# Ethernet.net
KiCad netlist of a schematic drawn in Altium Designer
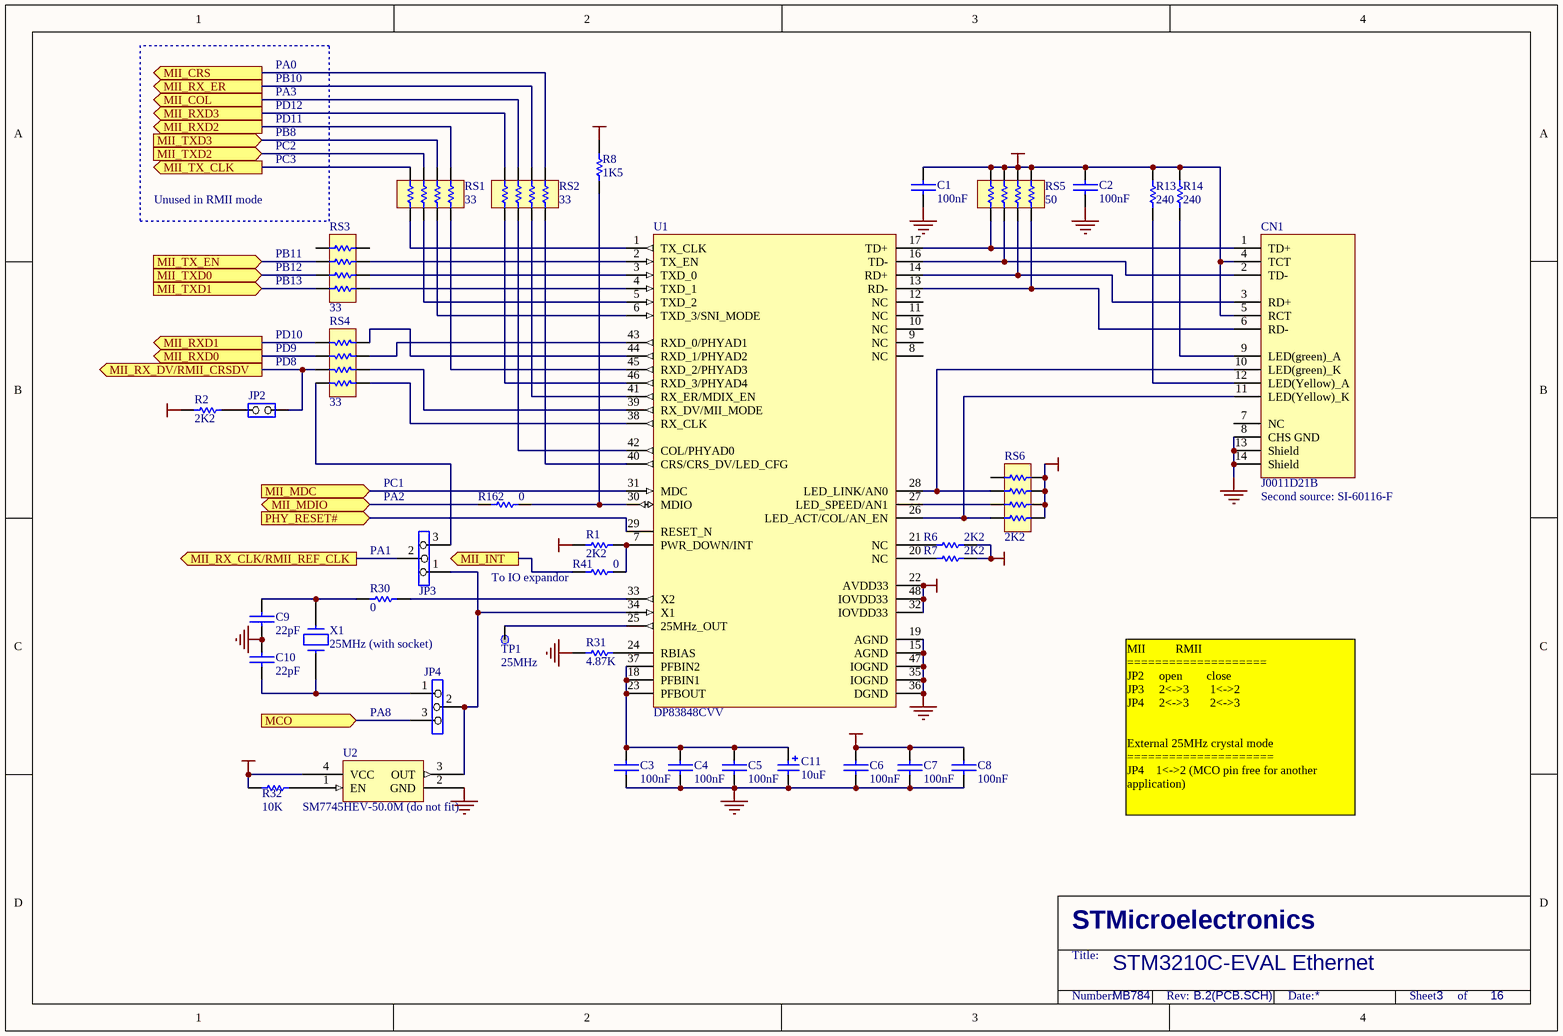
[diagram p0: Ethernet.SchDoc]

(export (version "E")
  (design (tool "Eeschema 10.0.6"))
  (components
    (comp (ref "C1")
      (value "100nF")
      (footprint "0603C")
      (description "Capacitor")
      (libsource (lib "*") (part "CAP"))
    )
    (comp (ref "C2")
      (value "100nF")
      (footprint "0603C")
      (description "Capacitor")
      (libsource (lib "*") (part "CAP"))
    )
    (comp (ref "C3")
      (value "100nF")
      (footprint "0603C")
      (description "Capacitor")
      (libsource (lib "*") (part "CAP"))
    )
    (comp (ref "C4")
      (value "100nF")
      (footprint "0603C")
      (description "Capacitor")
      (libsource (lib "*") (part "CAP"))
    )
    (comp (ref "C5")
      (value "100nF")
      (footprint "0603C")
      (description "Capacitor")
      (libsource (lib "*") (part "CAP"))
    )
    (comp (ref "C6")
      (value "100nF")
      (footprint "0603C")
      (description "Capacitor")
      (libsource (lib "*") (part "CAP"))
    )
    (comp (ref "C7")
      (value "100nF")
      (footprint "0603C")
      (description "Capacitor")
      (libsource (lib "*") (part "CAP"))
    )
    (comp (ref "C8")
      (value "100nF")
      (footprint "0603C")
      (description "Capacitor")
      (libsource (lib "*") (part "CAP"))
    )
    (comp (ref "C9")
      (value "22pF")
      (footprint "0603R")
      (description "Capacitor")
      (libsource (lib "*") (part "CAP"))
    )
    (comp (ref "C10")
      (value "22pF")
      (footprint "0603R")
      (description "Capacitor")
      (libsource (lib "*") (part "CAP"))
    )
    (comp (ref "C11")
      (value "10uF")
      (footprint "TAN-A")
      (description "Polarized Capacitor (Radial)")
      (fields (field (name "PUBLISHER") "Altium Limited"))
      (libsource (lib "Miscellaneous Devices") (part "Cap Pol1"))
    )
    (comp (ref "CN1")
      (value "J0011D21B")
      (footprint "J0011D21B")
      (libsource (lib "MB784") (part "J0011D21B"))
    )
    (comp (ref "JP2") (value "~") (footprint "SIP2") (libsource (lib "*") (part "JP2")))
    (comp (ref "JP3") (value "~") (footprint "SIP3") (libsource (lib "STR910_SCHLIB") (part "Jumper3")))
    (comp (ref "JP4") (value "~") (footprint "SIP3") (libsource (lib "STR910_SCHLIB") (part "Jumper3")))
    (comp (ref "R1")
      (value "2K2")
      (footprint "0603R")
      (description "Resistor")
      (fields (field (name "PUBLISHER") "Altium Limited"))
      (libsource (lib "Miscellaneous Devices") (part "Res1"))
    )
    (comp (ref "R2")
      (value "2K2")
      (footprint "0603R")
      (description "Resistor")
      (fields (field (name "PUBLISHER") "Altium Limited"))
      (libsource (lib "Miscellaneous Devices") (part "Res1"))
    )
    (comp (ref "R6")
      (value "2K2")
      (footprint "0603R")
      (description "Resistor")
      (fields (field (name "PUBLISHER") "Altium Limited"))
      (libsource (lib "Miscellaneous Devices") (part "Res1"))
    )
    (comp (ref "R7")
      (value "2K2")
      (footprint "0603R")
      (description "Resistor")
      (fields (field (name "PUBLISHER") "Altium Limited"))
      (libsource (lib "Miscellaneous Devices") (part "Res1"))
    )
    (comp (ref "R8")
      (value "1K5")
      (footprint "0603R")
      (description "Resistor")
      (fields (field (name "PUBLISHER") "Altium Limited"))
      (libsource (lib "Miscellaneous Devices") (part "Res1"))
    )
    (comp (ref "R13")
      (value "240")
      (footprint "0603R")
      (description "Resistor")
      (fields (field (name "PUBLISHER") "Altium Limited"))
      (libsource (lib "Miscellaneous Devices") (part "Res1"))
    )
    (comp (ref "R14")
      (value "240")
      (footprint "0603R")
      (description "Resistor")
      (fields (field (name "PUBLISHER") "Altium Limited"))
      (libsource (lib "Miscellaneous Devices") (part "Res1"))
    )
    (comp (ref "R30")
      (value "0")
      (footprint "0603R")
      (description "Resistor")
      (fields (field (name "PUBLISHER") "Altium Limited"))
      (libsource (lib "Miscellaneous Devices") (part "Res1"))
    )
    (comp (ref "R31")
      (value "4.87K")
      (footprint "0603R")
      (description "Resistor")
      (fields (field (name "PUBLISHER") "Altium Limited"))
      (libsource (lib "Miscellaneous Devices") (part "Res1"))
    )
    (comp (ref "R32")
      (value "10K")
      (footprint "0603R")
      (description "Resistor")
      (fields (field (name "PUBLISHER") "Altium Limited"))
      (libsource (lib "Miscellaneous Devices") (part "Res1"))
    )
    (comp (ref "R41")
      (value "0")
      (footprint "0603R")
      (description "Resistor")
      (fields (field (name "PUBLISHER") "Altium Limited"))
      (libsource (lib "Miscellaneous Devices") (part "Res1"))
    )
    (comp (ref "R162")
      (value "0")
      (footprint "0603R")
      (description "Resistor")
      (fields (field (name "PUBLISHER") "Altium Limited"))
      (libsource (lib "Miscellaneous Devices") (part "Res1"))
    )
    (comp (ref "RS1") (value "33") (footprint "RES-4B") (libsource (lib "MB784") (part "Resister Array")))
    (comp (ref "RS2") (value "33") (footprint "RES-4B") (libsource (lib "MB784") (part "Resister Array")))
    (comp (ref "RS3") (value "33") (footprint "RES-4B") (libsource (lib "") (part "Resister Array_2")))
    (comp (ref "RS4") (value "33") (footprint "RES-4B") (libsource (lib "*") (part "Resister Array")))
    (comp (ref "RS5") (value "50") (footprint "RES-4B") (libsource (lib "") (part "Resister Array_1")))
    (comp (ref "RS6") (value "2K2") (footprint "RES-4B") (libsource (lib "") (part "Resister Array_2")))
    (comp (ref "TP1") (value "25MHz") (footprint "TP") (libsource (lib "*") (part "TP")))
    (comp (ref "U1") (value "DP83848CVV") (footprint "LQFP48") (libsource (lib "MB784") (part "DP83848CVV")))
    (comp (ref "U2")
      (value "SM7745HEV-50.0M (do not fit)")
      (footprint "XTAL_5X7")
      (libsource (lib "MB784") (part "SM7745HEV-50.0M"))
    )
    (comp (ref "X1")
      (value "25MHz (with socket)")
      (footprint "XTAL1")
      (description "Crystal")
      (libsource (lib "*") (part "CRYSTAL"))
    )
  )
  (nets
    (net (code "1") (name "+3V3") (class "Default")
      (node (ref "C1") (pin "2") (pinfunction "2_2") (pintype "passive"))
      (node (ref "C2") (pin "2") (pinfunction "2_2") (pintype "passive"))
      (node (ref "C6") (pin "1") (pinfunction "1_1") (pintype "passive"))
      (node (ref "C7") (pin "2") (pinfunction "2_2") (pintype "passive"))
      (node (ref "C8") (pin "2") (pinfunction "2_2") (pintype "passive"))
      (node (ref "CN1") (pin "4") (pinfunction "TCT_4") (pintype "passive"))
      (node (ref "CN1") (pin "5") (pinfunction "RCT_5") (pintype "passive"))
      (node (ref "R1") (pin "1") (pinfunction "1_1") (pintype "passive"))
      (node (ref "R13") (pin "2") (pinfunction "2_2") (pintype "passive"))
      (node (ref "R14") (pin "2") (pinfunction "2_2") (pintype "passive"))
      (node (ref "R2") (pin "2") (pinfunction "2_2") (pintype "passive"))
      (node (ref "R32") (pin "1") (pinfunction "1_1") (pintype "passive"))
      (node (ref "R6") (pin "2") (pinfunction "2_2") (pintype "passive"))
      (node (ref "R7") (pin "2") (pinfunction "2_2") (pintype "passive"))
      (node (ref "R8") (pin "2") (pinfunction "2_2") (pintype "passive"))
      (node (ref "RS5") (pin "1") (pinfunction "1_1") (pintype "passive"))
      (node (ref "RS5") (pin "3") (pinfunction "3_3") (pintype "passive"))
      (node (ref "RS5") (pin "5") (pinfunction "5_5") (pintype "passive"))
      (node (ref "RS5") (pin "7") (pinfunction "7_7") (pintype "passive"))
      (node (ref "RS6") (pin "1") (pinfunction "1_1") (pintype "passive"))
      (node (ref "RS6") (pin "3") (pinfunction "3_3") (pintype "passive"))
      (node (ref "RS6") (pin "5") (pinfunction "5_5") (pintype "passive"))
      (node (ref "RS6") (pin "7") (pinfunction "7_7") (pintype "passive"))
      (node (ref "U1") (pin "22") (pinfunction "AVDD33_22") (pintype "passive"))
      (node (ref "U1") (pin "32") (pinfunction "IOVDD33_32") (pintype "passive"))
      (node (ref "U1") (pin "48") (pinfunction "IOVDD33_48") (pintype "passive"))
      (node (ref "U2") (pin "4") (pinfunction "VCC_4") (pintype "passive"))
    )
    (net (code "2") (name "/MCO") (class "Default") (node (ref "JP4") (pin "3") (pintype "passive")))
    (net (code "3") (name "/MII_COL") (class "Default")
      (node (ref "RS2") (pin "4") (pinfunction "4_4") (pintype "passive"))
    )
    (net (code "4") (name "/MII_CRS") (class "Default")
      (node (ref "RS2") (pin "8") (pinfunction "8_8") (pintype "passive"))
    )
    (net (code "5") (name "/MII_INT") (class "Default")
      (node (ref "R41") (pin "1") (pinfunction "1_1") (pintype "passive"))
    )
    (net (code "6") (name "/MII_MDC") (class "Default")
      (node (ref "U1") (pin "31") (pinfunction "MDC_31") (pintype "input"))
    )
    (net (code "7") (name "/MII_MDIO") (class "Default")
      (node (ref "R162") (pin "1") (pinfunction "1_1") (pintype "passive"))
    )
    (net (code "8") (name "/MII_RXD0") (class "Default")
      (node (ref "RS4") (pin "4") (pinfunction "4_4") (pintype "passive"))
    )
    (net (code "9") (name "/MII_RXD1") (class "Default")
      (node (ref "RS4") (pin "2") (pinfunction "2_2") (pintype "passive"))
    )
    (net (code "10") (name "/MII_RXD2") (class "Default")
      (node (ref "RS1") (pin "8") (pinfunction "8_8") (pintype "passive"))
    )
    (net (code "11") (name "/MII_RXD3") (class "Default")
      (node (ref "RS2") (pin "2") (pinfunction "2_2") (pintype "passive"))
    )
    (net (code "12") (name "/MII_RX_CLK{slash}RMII_REF_CLK") (class "Default")
      (node (ref "JP3") (pin "2") (pintype "passive"))
    )
    (net (code "13") (name "/MII_RX_DV{slash}RMII_CRSDV") (class "Default")
      (node (ref "JP2") (pin "1") (pinfunction "COMMON_1") (pintype "passive"))
      (node (ref "RS4") (pin "6") (pinfunction "6_6") (pintype "passive"))
    )
    (net (code "14") (name "/MII_RX_ER") (class "Default")
      (node (ref "RS2") (pin "6") (pinfunction "6_6") (pintype "passive"))
    )
    (net (code "15") (name "/MII_TXD0") (class "Default")
      (node (ref "RS3") (pin "4") (pinfunction "4_4") (pintype "passive"))
    )
    (net (code "16") (name "/MII_TXD1") (class "Default")
      (node (ref "RS3") (pin "2") (pinfunction "2_2") (pintype "passive"))
    )
    (net (code "17") (name "/MII_TXD2") (class "Default")
      (node (ref "RS1") (pin "4") (pinfunction "4_4") (pintype "passive"))
    )
    (net (code "18") (name "/MII_TXD3") (class "Default")
      (node (ref "RS1") (pin "6") (pinfunction "6_6") (pintype "passive"))
    )
    (net (code "19") (name "/MII_TX_CLK") (class "Default")
      (node (ref "RS1") (pin "2") (pinfunction "2_2") (pintype "passive"))
    )
    (net (code "20") (name "/MII_TX_EN") (class "Default")
      (node (ref "RS3") (pin "6") (pinfunction "6_6") (pintype "passive"))
    )
    (net (code "21") (name "/PHY_RESET#") (class "Default")
      (node (ref "U1") (pin "29") (pinfunction "RESET_N_29") (pintype "passive"))
    )
    (net (code "22") (name "GND") (class "Default")
      (node (ref "C1") (pin "1") (pinfunction "1_1") (pintype "passive"))
      (node (ref "C10") (pin "2") (pinfunction "2_2") (pintype "passive"))
      (node (ref "C11") (pin "2") (pinfunction "2_2") (pintype "passive"))
      (node (ref "C2") (pin "1") (pinfunction "1_1") (pintype "passive"))
      (node (ref "C3") (pin "2") (pinfunction "2_2") (pintype "passive"))
      (node (ref "C4") (pin "1") (pinfunction "1_1") (pintype "passive"))
      (node (ref "C5") (pin "1") (pinfunction "1_1") (pintype "passive"))
      (node (ref "C6") (pin "2") (pinfunction "2_2") (pintype "passive"))
      (node (ref "C7") (pin "1") (pinfunction "1_1") (pintype "passive"))
      (node (ref "C8") (pin "1") (pinfunction "1_1") (pintype "passive"))
      (node (ref "C9") (pin "1") (pinfunction "1_1") (pintype "passive"))
      (node (ref "CN1") (pin "13") (pinfunction "Shield_13") (pintype "passive"))
      (node (ref "CN1") (pin "14") (pinfunction "Shield_14") (pintype "passive"))
      (node (ref "CN1") (pin "8") (pinfunction "CHS_GND_8") (pintype "passive"))
      (node (ref "R31") (pin "1") (pinfunction "1_1") (pintype "passive"))
      (node (ref "U1") (pin "15") (pinfunction "AGND_15") (pintype "passive"))
      (node (ref "U1") (pin "19") (pinfunction "AGND_19") (pintype "passive"))
      (node (ref "U1") (pin "35") (pinfunction "IOGND_35") (pintype "passive"))
      (node (ref "U1") (pin "36") (pinfunction "DGND_36") (pintype "passive"))
      (node (ref "U1") (pin "47") (pinfunction "IOGND_47") (pintype "passive"))
      (node (ref "U2") (pin "2") (pinfunction "GND_2") (pintype "passive"))
    )
    (net (code "23") (name "Net-(C9-Pad2)") (class "Default")
      (node (ref "C9") (pin "2") (pinfunction "2_2") (pintype "passive"))
      (node (ref "R30") (pin "2") (pinfunction "2_2") (pintype "passive"))
      (node (ref "X1") (pin "2") (pinfunction "2_2") (pintype "passive"))
    )
    (net (code "24") (name "Net-(C10-Pad1)") (class "Default")
      (node (ref "C10") (pin "1") (pinfunction "1_1") (pintype "passive"))
      (node (ref "JP4") (pin "1") (pintype "passive"))
      (node (ref "X1") (pin "1") (pinfunction "1_1") (pintype "passive"))
    )
    (net (code "25") (name "Net-(CN1-LED(Yellow)_A)") (class "Default")
      (node (ref "CN1") (pin "12") (pinfunction "LED(Yellow)_A_12") (pintype "passive"))
      (node (ref "R13") (pin "1") (pinfunction "1_1") (pintype "passive"))
    )
    (net (code "26") (name "Net-(CN1-LED(Yellow)_K)") (class "Default")
      (node (ref "CN1") (pin "11") (pinfunction "LED(Yellow)_K_11") (pintype "passive"))
      (node (ref "RS6") (pin "2") (pinfunction "2_2") (pintype "passive"))
      (node (ref "U1") (pin "26") (pinfunction "LED_ACT/COL/AN_EN_26") (pintype "passive"))
    )
    (net (code "27") (name "Net-(CN1-LED(green)_A)") (class "Default")
      (node (ref "CN1") (pin "9") (pinfunction "LED(green)_A_9") (pintype "passive"))
      (node (ref "R14") (pin "1") (pinfunction "1_1") (pintype "passive"))
    )
    (net (code "28") (name "Net-(CN1-LED(green)_K)") (class "Default")
      (node (ref "CN1") (pin "10") (pinfunction "LED(green)_K_10") (pintype "passive"))
      (node (ref "RS6") (pin "6") (pinfunction "6_6") (pintype "passive"))
      (node (ref "U1") (pin "28") (pinfunction "LED_LINK/AN0_28") (pintype "passive"))
    )
    (net (code "29") (name "Net-(CN1-RD+)") (class "Default")
      (node (ref "CN1") (pin "3") (pinfunction "RD+_3") (pintype "passive"))
      (node (ref "RS5") (pin "4") (pinfunction "4_4") (pintype "passive"))
      (node (ref "U1") (pin "14") (pinfunction "RD+_14") (pintype "passive"))
    )
    (net (code "30") (name "Net-(CN1-RD-)") (class "Default")
      (node (ref "CN1") (pin "6") (pinfunction "RD-_6") (pintype "passive"))
      (node (ref "RS5") (pin "2") (pinfunction "2_2") (pintype "passive"))
      (node (ref "U1") (pin "13") (pinfunction "RD-_13") (pintype "passive"))
    )
    (net (code "31") (name "Net-(CN1-TD+)") (class "Default")
      (node (ref "CN1") (pin "1") (pinfunction "TD+_1") (pintype "passive"))
      (node (ref "RS5") (pin "8") (pinfunction "8_8") (pintype "passive"))
      (node (ref "U1") (pin "17") (pinfunction "TD+_17") (pintype "passive"))
    )
    (net (code "32") (name "Net-(CN1-TD-)") (class "Default")
      (node (ref "CN1") (pin "2") (pinfunction "TD-_2") (pintype "passive"))
      (node (ref "RS5") (pin "6") (pinfunction "6_6") (pintype "passive"))
      (node (ref "U1") (pin "16") (pinfunction "TD-_16") (pintype "passive"))
    )
    (net (code "33") (name "Net-(JP2-NO)") (class "Default")
      (node (ref "JP2") (pin "2") (pinfunction "NO_2") (pintype "passive"))
      (node (ref "R2") (pin "1") (pinfunction "1_1") (pintype "passive"))
    )
    (net (code "34") (name "Net-(JP3-Pad3)") (class "Default")
      (node (ref "JP3") (pin "3") (pintype "passive"))
      (node (ref "RS4") (pin "8") (pinfunction "8_8") (pintype "passive"))
    )
    (net (code "35") (name "Net-(R6-Pad1)") (class "Default")
      (node (ref "R6") (pin "1") (pinfunction "1_1") (pintype "passive"))
      (node (ref "U1") (pin "21") (pinfunction "NC_21") (pintype "passive"))
    )
    (net (code "36") (name "Net-(R7-Pad1)") (class "Default")
      (node (ref "R7") (pin "1") (pinfunction "1_1") (pintype "passive"))
      (node (ref "U1") (pin "20") (pinfunction "NC_20") (pintype "passive"))
    )
    (net (code "37") (name "Net-(U1-25MHz_OUT)") (class "Default")
      (node (ref "TP1") (pin "1") (pinfunction "1_1") (pintype "passive"))
      (node (ref "U1") (pin "25") (pinfunction "25MHz_OUT_25") (pintype "output"))
    )
    (net (code "38") (name "Net-(U1-COL{slash}PHYAD0)") (class "Default")
      (node (ref "RS2") (pin "3") (pinfunction "3_3") (pintype "passive"))
      (node (ref "U1") (pin "42") (pinfunction "COL/PHYAD0_42") (pintype "output"))
    )
    (net (code "39") (name "Net-(U1-CRS{slash}CRS_DV{slash}LED_CFG)") (class "Default")
      (node (ref "RS2") (pin "7") (pinfunction "7_7") (pintype "passive"))
      (node (ref "U1") (pin "40") (pinfunction "CRS/CRS_DV/LED_CFG_40") (pintype "output"))
    )
    (net (code "40") (name "Net-(U1-LED_SPEED{slash}AN1)") (class "Default")
      (node (ref "RS6") (pin "4") (pinfunction "4_4") (pintype "passive"))
      (node (ref "U1") (pin "27") (pinfunction "LED_SPEED/AN1_27") (pintype "passive"))
    )
    (net (code "41") (name "Net-(U1-MDIO)") (class "Default")
      (node (ref "R162") (pin "2") (pinfunction "2_2") (pintype "passive"))
      (node (ref "R8") (pin "1") (pinfunction "1_1") (pintype "passive"))
      (node (ref "U1") (pin "30") (pinfunction "MDIO_30") (pintype "bidirectional"))
    )
    (net (code "42") (name "Net-(U1-PFBIN1)") (class "Default")
      (node (ref "C11") (pin "1") (pinfunction "1_1") (pintype "passive"))
      (node (ref "C3") (pin "1") (pinfunction "1_1") (pintype "passive"))
      (node (ref "C4") (pin "2") (pinfunction "2_2") (pintype "passive"))
      (node (ref "C5") (pin "2") (pinfunction "2_2") (pintype "passive"))
      (node (ref "U1") (pin "18") (pinfunction "PFBIN1_18") (pintype "passive"))
      (node (ref "U1") (pin "23") (pinfunction "PFBOUT_23") (pintype "passive"))
      (node (ref "U1") (pin "37") (pinfunction "PFBIN2_37") (pintype "passive"))
    )
    (net (code "43") (name "Net-(U1-PWR_DOWN{slash}INT)") (class "Default")
      (node (ref "R1") (pin "2") (pinfunction "2_2") (pintype "passive"))
      (node (ref "R41") (pin "2") (pinfunction "2_2") (pintype "passive"))
      (node (ref "U1") (pin "7") (pinfunction "PWR_DOWN/INT_7") (pintype "passive"))
    )
    (net (code "44") (name "Net-(U1-RBIAS)") (class "Default")
      (node (ref "R31") (pin "2") (pinfunction "2_2") (pintype "passive"))
      (node (ref "U1") (pin "24") (pinfunction "RBIAS_24") (pintype "passive"))
    )
    (net (code "45") (name "Net-(U1-RXD_0{slash}PHYAD1)") (class "Default")
      (node (ref "RS4") (pin "3") (pinfunction "3_3") (pintype "passive"))
      (node (ref "U1") (pin "43") (pinfunction "RXD_0/PHYAD1_43") (pintype "output"))
    )
    (net (code "46") (name "Net-(U1-RXD_1{slash}PHYAD2)") (class "Default")
      (node (ref "RS4") (pin "1") (pinfunction "1_1") (pintype "passive"))
      (node (ref "U1") (pin "44") (pinfunction "RXD_1/PHYAD2_44") (pintype "output"))
    )
    (net (code "47") (name "Net-(U1-RXD_2{slash}PHYAD3)") (class "Default")
      (node (ref "RS1") (pin "7") (pinfunction "7_7") (pintype "passive"))
      (node (ref "U1") (pin "45") (pinfunction "RXD_2/PHYAD3_45") (pintype "output"))
    )
    (net (code "48") (name "Net-(U1-RXD_3{slash}PHYAD4)") (class "Default")
      (node (ref "RS2") (pin "1") (pinfunction "1_1") (pintype "passive"))
      (node (ref "U1") (pin "46") (pinfunction "RXD_3/PHYAD4_46") (pintype "output"))
    )
    (net (code "49") (name "Net-(U1-RX_CLK)") (class "Default")
      (node (ref "RS4") (pin "7") (pinfunction "7_7") (pintype "passive"))
      (node (ref "U1") (pin "38") (pinfunction "RX_CLK_38") (pintype "output"))
    )
    (net (code "50") (name "Net-(U1-RX_DV{slash}MII_MODE)") (class "Default")
      (node (ref "RS4") (pin "5") (pinfunction "5_5") (pintype "passive"))
      (node (ref "U1") (pin "39") (pinfunction "RX_DV/MII_MODE_39") (pintype "output"))
    )
    (net (code "51") (name "Net-(U1-RX_ER{slash}MDIX_EN)") (class "Default")
      (node (ref "RS2") (pin "5") (pinfunction "5_5") (pintype "passive"))
      (node (ref "U1") (pin "41") (pinfunction "RX_ER/MDIX_EN_41") (pintype "output"))
    )
    (net (code "52") (name "Net-(U1-TXD_0)") (class "Default")
      (node (ref "RS3") (pin "3") (pinfunction "3_3") (pintype "passive"))
      (node (ref "U1") (pin "3") (pinfunction "TXD_0_3") (pintype "input"))
    )
    (net (code "53") (name "Net-(U1-TXD_1)") (class "Default")
      (node (ref "RS3") (pin "1") (pinfunction "1_1") (pintype "passive"))
      (node (ref "U1") (pin "4") (pinfunction "TXD_1_4") (pintype "input"))
    )
    (net (code "54") (name "Net-(U1-TXD_2)") (class "Default")
      (node (ref "RS1") (pin "3") (pinfunction "3_3") (pintype "passive"))
      (node (ref "U1") (pin "5") (pinfunction "TXD_2_5") (pintype "input"))
    )
    (net (code "55") (name "Net-(U1-TXD_3{slash}SNI_MODE)") (class "Default")
      (node (ref "RS1") (pin "5") (pinfunction "5_5") (pintype "passive"))
      (node (ref "U1") (pin "6") (pinfunction "TXD_3/SNI_MODE_6") (pintype "input"))
    )
    (net (code "56") (name "Net-(U1-TX_CLK)") (class "Default")
      (node (ref "RS1") (pin "1") (pinfunction "1_1") (pintype "passive"))
      (node (ref "U1") (pin "1") (pinfunction "TX_CLK_1") (pintype "output"))
    )
    (net (code "57") (name "Net-(U1-TX_EN)") (class "Default")
      (node (ref "RS3") (pin "5") (pinfunction "5_5") (pintype "passive"))
      (node (ref "U1") (pin "2") (pinfunction "TX_EN_2") (pintype "input"))
    )
    (net (code "58") (name "Net-(U1-X1)") (class "Default")
      (node (ref "JP3") (pin "1") (pintype "passive"))
      (node (ref "JP4") (pin "2") (pintype "passive"))
      (node (ref "U1") (pin "34") (pinfunction "X1_34") (pintype "input"))
      (node (ref "U2") (pin "3") (pinfunction "OUT_3") (pintype "output"))
    )
    (net (code "59") (name "Net-(U1-X2)") (class "Default")
      (node (ref "R30") (pin "1") (pinfunction "1_1") (pintype "passive"))
      (node (ref "U1") (pin "33") (pinfunction "X2_33") (pintype "output"))
    )
    (net (code "60") (name "Net-(U2-EN)") (class "Default")
      (node (ref "R32") (pin "2") (pinfunction "2_2") (pintype "passive"))
      (node (ref "U2") (pin "1") (pinfunction "EN_1") (pintype "input"))
    )
    (net (code "61") (name "unconnected-(CN1-NC-Pad7)") (class "Default")
      (node (ref "CN1") (pin "7") (pinfunction "NC_7") (pintype "passive"))
    )
    (net (code "62") (name "unconnected-(RS3-Pad7)") (class "Default")
      (node (ref "RS3") (pin "7") (pinfunction "7_7") (pintype "passive"))
    )
    (net (code "63") (name "unconnected-(RS3-Pad8)") (class "Default")
      (node (ref "RS3") (pin "8") (pinfunction "8_8") (pintype "passive"))
    )
    (net (code "64") (name "unconnected-(RS6-Pad8)") (class "Default")
      (node (ref "RS6") (pin "8") (pinfunction "8_8") (pintype "passive"))
    )
    (net (code "65") (name "unconnected-(U1-NC-Pad8)") (class "Default")
      (node (ref "U1") (pin "8") (pinfunction "NC_8") (pintype "passive"))
    )
    (net (code "66") (name "unconnected-(U1-NC-Pad9)") (class "Default")
      (node (ref "U1") (pin "9") (pinfunction "NC_9") (pintype "passive"))
    )
    (net (code "67") (name "unconnected-(U1-NC-Pad10)") (class "Default")
      (node (ref "U1") (pin "10") (pinfunction "NC_10") (pintype "passive"))
    )
    (net (code "68") (name "unconnected-(U1-NC-Pad11)") (class "Default")
      (node (ref "U1") (pin "11") (pinfunction "NC_11") (pintype "passive"))
    )
    (net (code "69") (name "unconnected-(U1-NC-Pad12)") (class "Default")
      (node (ref "U1") (pin "12") (pinfunction "NC_12") (pintype "passive"))
    )
  )
)
